# DAUGHTER_SENSOR_JUMPER.net
KiCad netlist of a schematic drawn in EAGLE
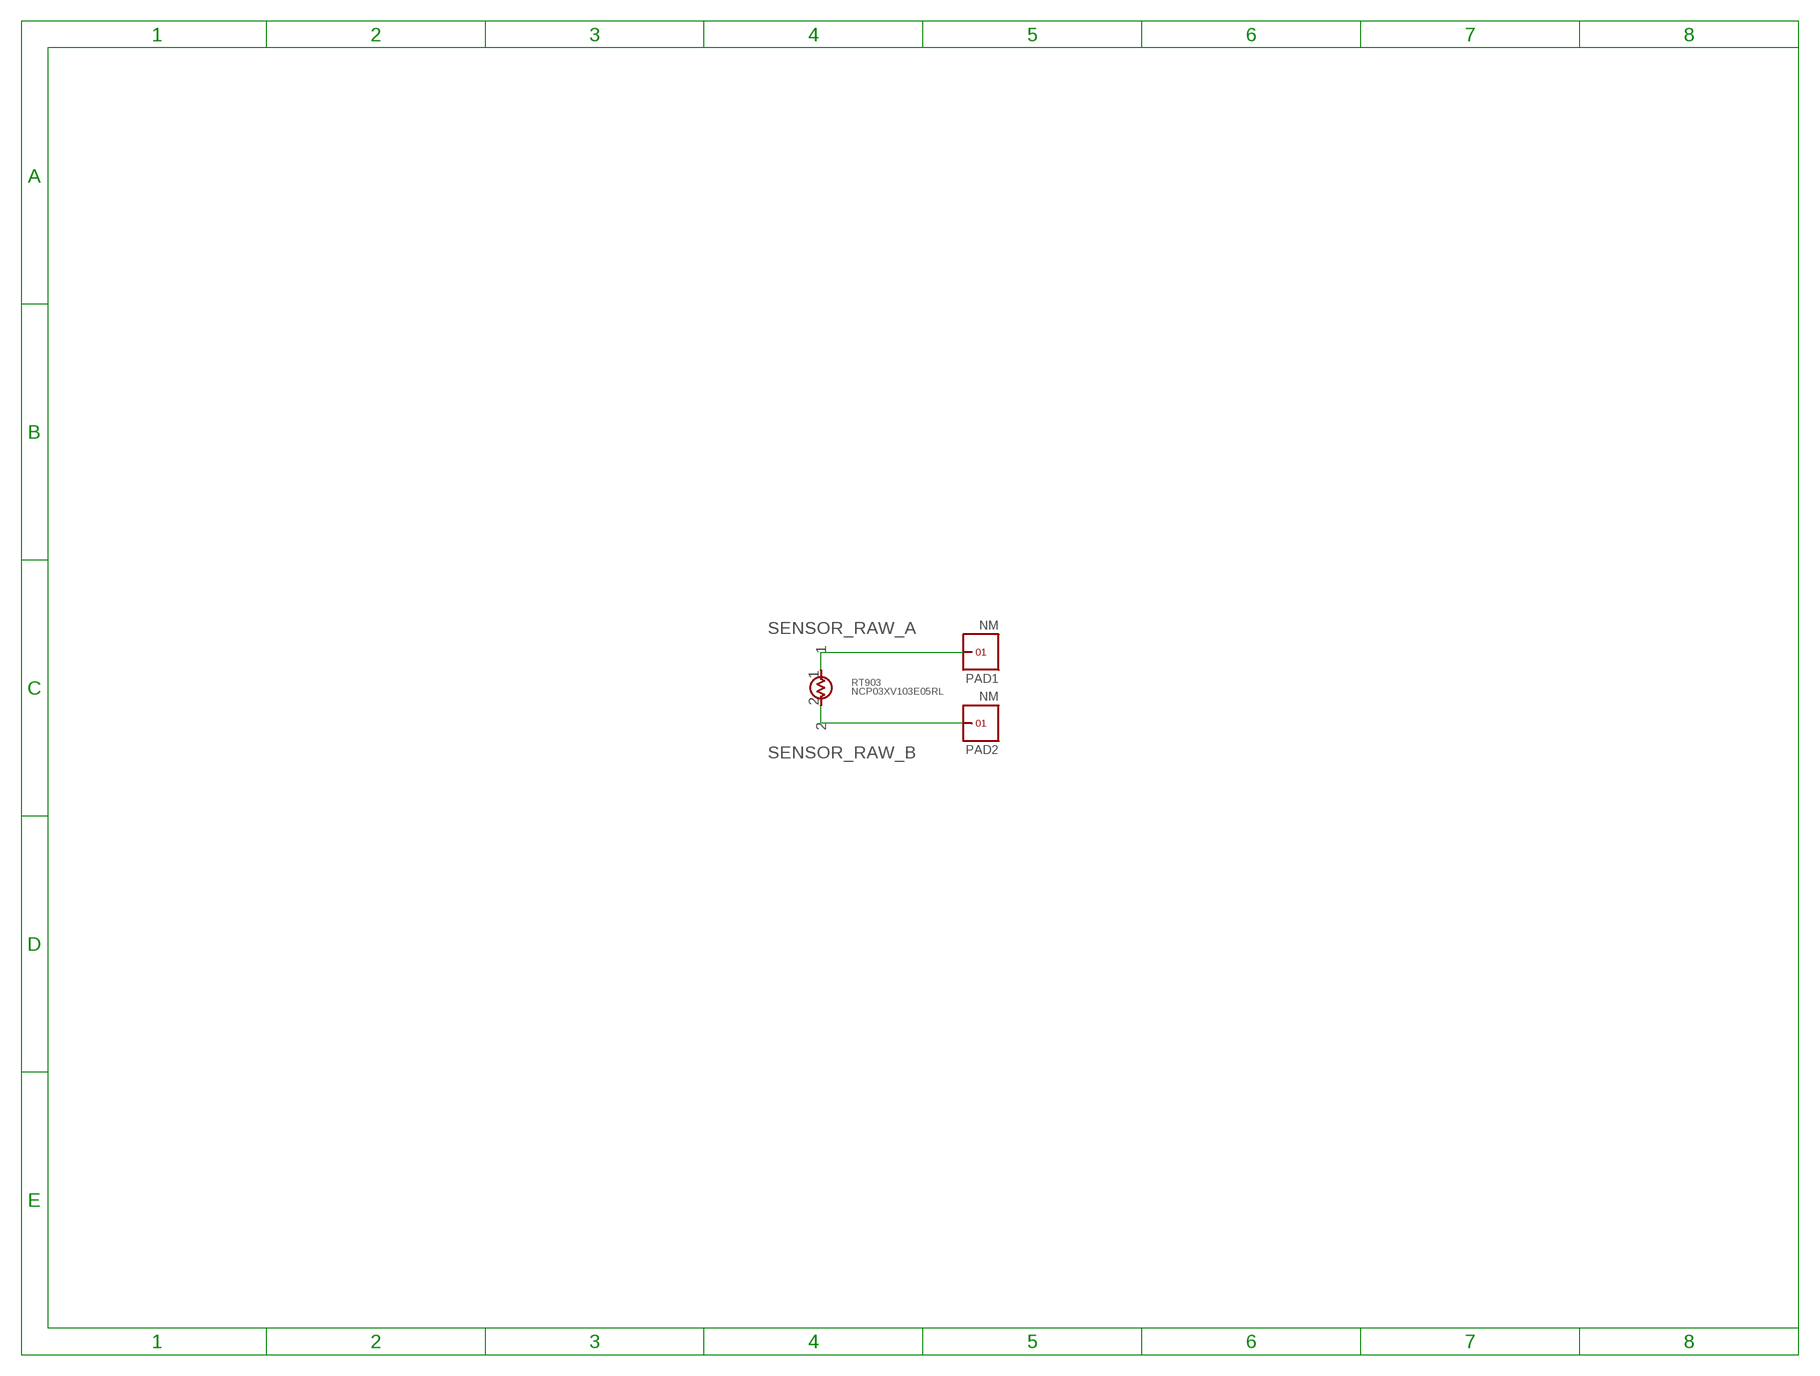
[diagram p0: schematic, sheet 1]

(export (version "E")
  (design (tool "Eeschema 10.0.6"))
  (components
    (comp (ref "PAD1")
      (value "NM")
      (footprint "eagle-import:PAD_2X3")
      (libsource (lib "eagle-import") (part "PUCK"))
    )
    (comp (ref "PAD2")
      (value "NM")
      (footprint "eagle-import:PAD_2X3")
      (libsource (lib "eagle-import") (part "PUCK"))
    )
    (comp (ref "RT903")
      (value "NCP03XV103E05RL")
      (footprint "eagle-import:0201")
      (fields (field (name "MPN") "NCP03XV103XV103E05RL/NTCG0603UH103HT"))
      (libsource (lib "eagle-import") (part "THERMISTOR"))
    )
  )
  (nets
    (net (code "1") (name "/SENSOR_RAW_A") (class "Default")
      (node (ref "PAD1") (pin "1") (pinfunction "1_1") (pintype "bidirectional"))
      (node (ref "RT903") (pin "1") (pinfunction "1_1") (pintype "bidirectional"))
    )
    (net (code "2") (name "/SENSOR_RAW_B") (class "Default")
      (node (ref "PAD2") (pin "1") (pinfunction "1_1") (pintype "bidirectional"))
      (node (ref "RT903") (pin "2") (pinfunction "2_2") (pintype "bidirectional"))
    )
  )
)
